# dev_efm32_tg.net
KiCad netlist of a schematic drawn in EAGLE
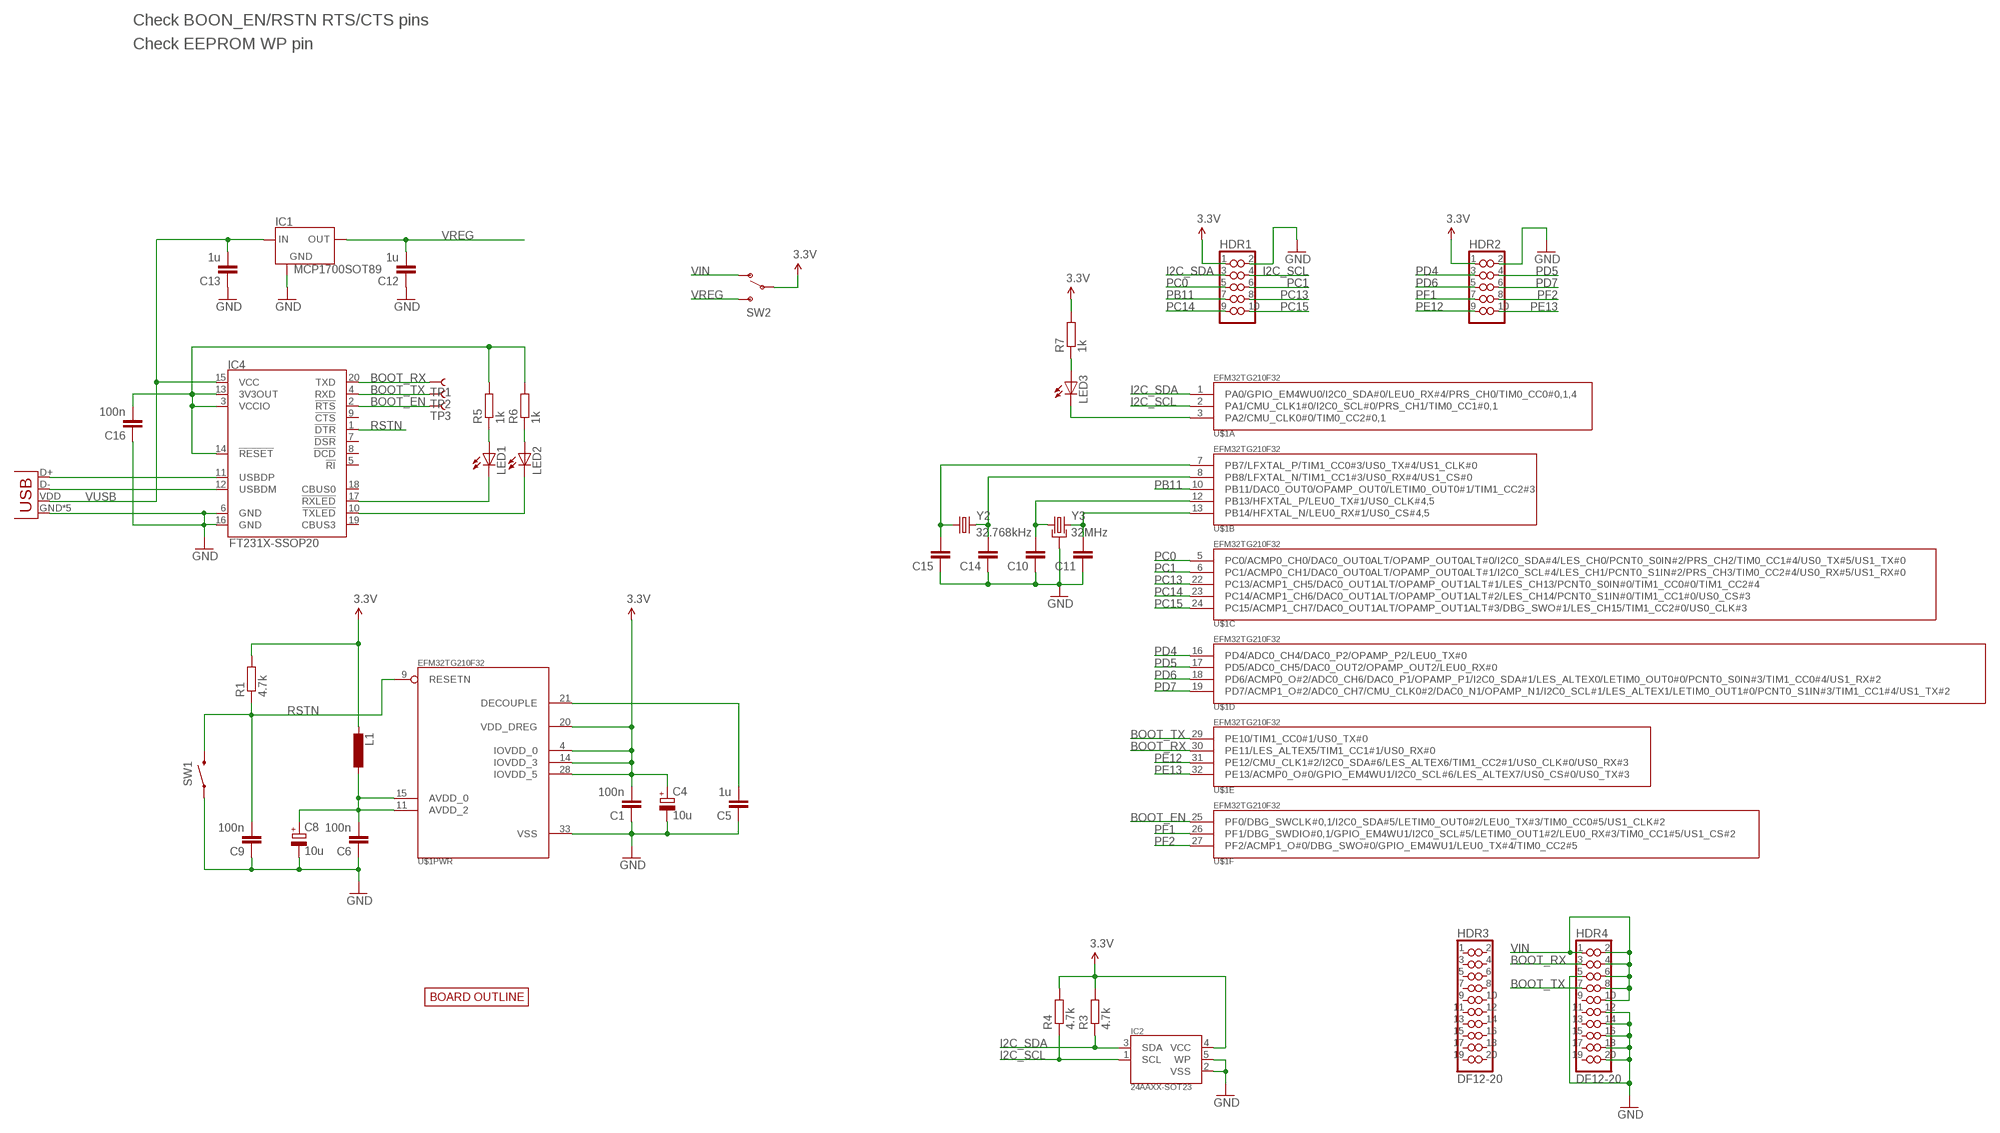
[diagram p0: schematic, sheet 1]

(export (version "E")
  (design (tool "Eeschema 10.0.6"))
  (components
    (comp (ref "C1")
      (value "100n")
      (footprint "eagle-import:0402")
      (libsource (lib "eagle-import") (part "C-0402"))
    )
    (comp (ref "C4")
      (value "10u")
      (footprint "eagle-import:CAP_CASE_A")
      (libsource (lib "eagle-import") (part "CPOL-A"))
    )
    (comp (ref "C5")
      (value "1u")
      (footprint "eagle-import:0402")
      (libsource (lib "eagle-import") (part "C-0402"))
    )
    (comp (ref "C6")
      (value "100n")
      (footprint "eagle-import:0402")
      (libsource (lib "eagle-import") (part "C-0402"))
    )
    (comp (ref "C8")
      (value "10u")
      (footprint "eagle-import:CAP_CASE_A")
      (libsource (lib "eagle-import") (part "CPOL-A"))
    )
    (comp (ref "C9")
      (value "100n")
      (footprint "eagle-import:0402")
      (libsource (lib "eagle-import") (part "C-0402"))
    )
    (comp (ref "C10")
      (value "C-0402")
      (footprint "eagle-import:0402")
      (libsource (lib "eagle-import") (part "C-0402"))
    )
    (comp (ref "C11")
      (value "C-0402")
      (footprint "eagle-import:0402")
      (libsource (lib "eagle-import") (part "C-0402"))
    )
    (comp (ref "C12")
      (value "1u")
      (footprint "eagle-import:0402")
      (libsource (lib "eagle-import") (part "C-0402"))
    )
    (comp (ref "C13")
      (value "1u")
      (footprint "eagle-import:0402")
      (libsource (lib "eagle-import") (part "C-0402"))
    )
    (comp (ref "C14")
      (value "C-0402")
      (footprint "eagle-import:0402")
      (libsource (lib "eagle-import") (part "C-0402"))
    )
    (comp (ref "C15")
      (value "C-0402")
      (footprint "eagle-import:0402")
      (libsource (lib "eagle-import") (part "C-0402"))
    )
    (comp (ref "C16")
      (value "100n")
      (footprint "eagle-import:0402")
      (libsource (lib "eagle-import") (part "C-0402"))
    )
    (comp (ref "HDR1")
      (value "HDR2X05-ROUND")
      (footprint "eagle-import:2X05ROUND")
      (libsource (lib "eagle-import") (part "HDR2X05-ROUND"))
    )
    (comp (ref "HDR2")
      (value "HDR2X05-ROUND")
      (footprint "eagle-import:2X05ROUND")
      (libsource (lib "eagle-import") (part "HDR2X05-ROUND"))
    )
    (comp (ref "HDR3")
      (value "DF12-20")
      (footprint "eagle-import:DF12_20_MF")
      (libsource (lib "eagle-import") (part "DF12-20"))
    )
    (comp (ref "HDR4")
      (value "DF12-20")
      (footprint "eagle-import:DF12_20_MF")
      (libsource (lib "eagle-import") (part "DF12-20"))
    )
    (comp (ref "IC1")
      (value "MCP1700SOT89")
      (footprint "eagle-import:SOT89")
      (libsource (lib "eagle-import") (part "MCP1700SOT89"))
    )
    (comp (ref "IC2")
      (value "24AAXX-SOT23")
      (footprint "eagle-import:SOT23-5")
      (libsource (lib "eagle-import") (part "24AAXX-SOT23"))
    )
    (comp (ref "IC4")
      (value "FT231X-SSOP20")
      (footprint "eagle-import:SSOP20")
      (libsource (lib "eagle-import") (part "FT231X-SSOP20"))
    )
    (comp (ref "L1")
      (value "L-0402")
      (footprint "eagle-import:0402")
      (libsource (lib "eagle-import") (part "L-0402"))
    )
    (comp (ref "LED1")
      (value "LED0603")
      (footprint "eagle-import:LED-0603")
      (libsource (lib "eagle-import") (part "LED0603"))
    )
    (comp (ref "LED2")
      (value "LED0603")
      (footprint "eagle-import:LED-0603")
      (libsource (lib "eagle-import") (part "LED0603"))
    )
    (comp (ref "LED3")
      (value "LED0603")
      (footprint "eagle-import:LED-0603")
      (libsource (lib "eagle-import") (part "LED0603"))
    )
    (comp (ref "R1")
      (value "4.7k")
      (footprint "eagle-import:0402")
      (libsource (lib "eagle-import") (part "R-0402"))
    )
    (comp (ref "R3")
      (value "4.7k")
      (footprint "eagle-import:0402")
      (libsource (lib "eagle-import") (part "R-0402"))
    )
    (comp (ref "R4")
      (value "4.7k")
      (footprint "eagle-import:0402")
      (libsource (lib "eagle-import") (part "R-0402"))
    )
    (comp (ref "R5")
      (value "1k")
      (footprint "eagle-import:0402")
      (libsource (lib "eagle-import") (part "R-0402"))
    )
    (comp (ref "R6")
      (value "1k")
      (footprint "eagle-import:0402")
      (libsource (lib "eagle-import") (part "R-0402"))
    )
    (comp (ref "R7")
      (value "1k")
      (footprint "eagle-import:0402")
      (libsource (lib "eagle-import") (part "R-0402"))
    )
    (comp (ref "SW1")
      (value "SWITCH_TACTILE-B3U-1000P")
      (footprint "eagle-import:B3U-1000P")
      (libsource (lib "eagle-import") (part "SWITCH_TACTILE-B3U-1000P"))
    )
    (comp (ref "SW2")
      (value "SWITCH_SPDT-PCM")
      (footprint "eagle-import:PCM12SMTR")
      (libsource (lib "eagle-import") (part "SWITCH_SPDT-PCM"))
    )
    (comp (ref "TP1")
      (value "TP_1X1-1")
      (footprint "eagle-import:TP_1X1_1")
      (libsource (lib "eagle-import") (part "TP_1X1-1"))
    )
    (comp (ref "TP2")
      (value "TP_1X1-1")
      (footprint "eagle-import:TP_1X1_1")
      (libsource (lib "eagle-import") (part "TP_1X1-1"))
    )
    (comp (ref "TP3")
      (value "TP_1X1-1")
      (footprint "eagle-import:TP_1X1_1")
      (libsource (lib "eagle-import") (part "TP_1X1-1"))
    )
    (comp (ref "U$1")
      (value "EFM32TG210F32")
      (footprint "eagle-import:QFN32")
      (libsource (lib "eagle-import") (part "EFM32TG210F32"))
    )
    (comp (ref "U$2")
      (value "USB-MICRO")
      (footprint "eagle-import:10118194_0001LF")
      (libsource (lib "eagle-import") (part "USB-MICRO"))
    )
    (comp (ref "U$3")
      (value "QK-OUTLINE")
      (footprint "eagle-import:QK-OUTLINE")
      (libsource (lib "eagle-import") (part "QK-OUTLINE"))
    )
    (comp (ref "Y2")
      (value "32.768kHz")
      (footprint "eagle-import:ABS07")
      (libsource (lib "eagle-import") (part "CRYSTAL-2-ABS07"))
    )
    (comp (ref "Y3")
      (value "32MHz")
      (footprint "eagle-import:ABM8G")
      (libsource (lib "eagle-import") (part "CRYSTAL-4-ABM8G"))
    )
  )
  (nets
    (net (code "1") (name "/BOOT_EN") (class "Default")
      (node (ref "IC4") (pin "2") (pinfunction "~{RTS}_2") (pintype "bidirectional"))
      (node (ref "TP3") (pin "P$1") (pinfunction "1_P$1") (pintype "bidirectional"))
      (node (ref "U$1") (pin "25") (pinfunction "PF0/DBG_SWCLK#0,1/I2C0_SDA#5/LETIM0_OUT0#2/LEU0_TX#3/TIM0_CC0#5/US1_CLK#2_25") (pintype "bidirectional"))
    )
    (net (code "2") (name "/BOOT_RX") (class "Default")
      (node (ref "HDR4") (pin "3") (pinfunction "3_3") (pintype "passive"))
      (node (ref "IC4") (pin "20") (pinfunction "TXD_20") (pintype "bidirectional"))
      (node (ref "TP1") (pin "P$1") (pinfunction "1_P$1") (pintype "bidirectional"))
      (node (ref "U$1") (pin "30") (pinfunction "PE11/LES_ALTEX5/TIM1_CC1#1/US0_RX#0_30") (pintype "bidirectional"))
    )
    (net (code "3") (name "/BOOT_TX") (class "Default")
      (node (ref "HDR4") (pin "7") (pinfunction "7_7") (pintype "passive"))
      (node (ref "IC4") (pin "4") (pinfunction "RXD_4") (pintype "bidirectional"))
      (node (ref "TP2") (pin "P$1") (pinfunction "1_P$1") (pintype "bidirectional"))
      (node (ref "U$1") (pin "29") (pinfunction "PE10/TIM1_CC0#1/US0_TX#0_29") (pintype "bidirectional"))
    )
    (net (code "4") (name "/I2C_SCL") (class "Default")
      (node (ref "HDR1") (pin "4") (pinfunction "4_4") (pintype "passive"))
      (node (ref "IC2") (pin "1") (pinfunction "SCL_1") (pintype "bidirectional"))
      (node (ref "R4") (pin "1") (pinfunction "1_1") (pintype "passive"))
      (node (ref "U$1") (pin "2") (pinfunction "PA1/CMU_CLK1#0/I2C0_SCL#0/PRS_CH1/TIM0_CC1#0,1_2") (pintype "bidirectional"))
    )
    (net (code "5") (name "/I2C_SDA") (class "Default")
      (node (ref "HDR1") (pin "3") (pinfunction "3_3") (pintype "passive"))
      (node (ref "IC2") (pin "3") (pinfunction "SDA_3") (pintype "bidirectional"))
      (node (ref "R3") (pin "1") (pinfunction "1_1") (pintype "passive"))
      (node (ref "U$1") (pin "1") (pinfunction "PA0/GPIO_EM4WU0/I2C0_SDA#0/LEU0_RX#4/PRS_CH0/TIM0_CC0#0,1,4_1") (pintype "bidirectional"))
    )
    (net (code "6") (name "/PB11") (class "Default")
      (node (ref "HDR1") (pin "7") (pinfunction "7_7") (pintype "passive"))
      (node (ref "U$1") (pin "10") (pinfunction "PB11/DAC0_OUT0/OPAMP_OUT0/LETIM0_OUT0#1/TIM1_CC2#3_10") (pintype "bidirectional"))
    )
    (net (code "7") (name "/PC0") (class "Default")
      (node (ref "HDR1") (pin "5") (pinfunction "5_5") (pintype "passive"))
      (node (ref "U$1") (pin "5") (pinfunction "PC0/ACMP0_CH0/DAC0_OUT0ALT/OPAMP_OUT0ALT#0/I2C0_SDA#4/LES_CH0/PCNT0_S0IN#2/PRS_CH2/TIM0_CC1#4/US0_TX#5/US1_TX#0_5") (pintype "bidirectional"))
    )
    (net (code "8") (name "/PC1") (class "Default")
      (node (ref "HDR1") (pin "6") (pinfunction "6_6") (pintype "passive"))
      (node (ref "U$1") (pin "6") (pinfunction "PC1/ACMP0_CH1/DAC0_OUT0ALT/OPAMP_OUT0ALT#1/I2C0_SCL#4/LES_CH1/PCNT0_S1IN#2/PRS_CH3/TIM0_CC2#4/US0_RX#5/US1_RX#0_6") (pintype "bidirectional"))
    )
    (net (code "9") (name "/PC13") (class "Default")
      (node (ref "HDR1") (pin "8") (pinfunction "8_8") (pintype "passive"))
      (node (ref "U$1") (pin "22") (pinfunction "PC13/ACMP1_CH5/DAC0_OUT1ALT/OPAMP_OUT1ALT#1/LES_CH13/PCNT0_S0IN#0/TIM1_CC0#0/TIM1_CC2#4_22") (pintype "bidirectional"))
    )
    (net (code "10") (name "/PC14") (class "Default")
      (node (ref "HDR1") (pin "9") (pinfunction "9_9") (pintype "passive"))
      (node (ref "U$1") (pin "23") (pinfunction "PC14/ACMP1_CH6/DAC0_OUT1ALT/OPAMP_OUT1ALT#2/LES_CH14/PCNT0_S1IN#0/TIM1_CC1#0/US0_CS#3_23") (pintype "bidirectional"))
    )
    (net (code "11") (name "/PC15") (class "Default")
      (node (ref "HDR1") (pin "10") (pinfunction "10_10") (pintype "passive"))
      (node (ref "U$1") (pin "24") (pinfunction "PC15/ACMP1_CH7/DAC0_OUT1ALT/OPAMP_OUT1ALT#3/DBG_SWO#1/LES_CH15/TIM1_CC2#0/US0_CLK#3_24") (pintype "bidirectional"))
    )
    (net (code "12") (name "/PD4") (class "Default")
      (node (ref "HDR2") (pin "3") (pinfunction "3_3") (pintype "passive"))
      (node (ref "U$1") (pin "16") (pinfunction "PD4/ADC0_CH4/DAC0_P2/OPAMP_P2/LEU0_TX#0_16") (pintype "bidirectional"))
    )
    (net (code "13") (name "/PD5") (class "Default")
      (node (ref "HDR2") (pin "4") (pinfunction "4_4") (pintype "passive"))
      (node (ref "U$1") (pin "17") (pinfunction "PD5/ADC0_CH5/DAC0_OUT2/OPAMP_OUT2/LEU0_RX#0_17") (pintype "bidirectional"))
    )
    (net (code "14") (name "/PD6") (class "Default")
      (node (ref "HDR2") (pin "5") (pinfunction "5_5") (pintype "passive"))
      (node (ref "U$1") (pin "18") (pinfunction "PD6/ACMP0_O#2/ADC0_CH6/DAC0_P1/OPAMP_P1/I2C0_SDA#1/LES_ALTEX0/LETIM0_OUT0#0/PCNT0_S0IN#3/TIM1_CC0#4/US1_RX#2_18") (pintype "bidirectional"))
    )
    (net (code "15") (name "/PD7") (class "Default")
      (node (ref "HDR2") (pin "6") (pinfunction "6_6") (pintype "passive"))
      (node (ref "U$1") (pin "19") (pinfunction "PD7/ACMP1_O#2/ADC0_CH7/CMU_CLK0#2/DAC0_N1/OPAMP_N1/I2C0_SCL#1/LES_ALTEX1/LETIM0_OUT1#0/PCNT0_S1IN#3/TIM1_CC1#4/US1_TX#2_19") (pintype "bidirectional"))
    )
    (net (code "16") (name "/PE12") (class "Default")
      (node (ref "HDR2") (pin "9") (pinfunction "9_9") (pintype "passive"))
      (node (ref "U$1") (pin "31") (pinfunction "PE12/CMU_CLK1#2/I2C0_SDA#6/LES_ALTEX6/TIM1_CC2#1/US0_CLK#0/US0_RX#3_31") (pintype "bidirectional"))
    )
    (net (code "17") (name "/PE13") (class "Default")
      (node (ref "HDR2") (pin "10") (pinfunction "10_10") (pintype "passive"))
      (node (ref "U$1") (pin "32") (pinfunction "PE13/ACMP0_O#0/GPIO_EM4WU1/I2C0_SCL#6/LES_ALTEX7/US0_CS#0/US0_TX#3_32") (pintype "bidirectional"))
    )
    (net (code "18") (name "/PF1") (class "Default")
      (node (ref "HDR2") (pin "7") (pinfunction "7_7") (pintype "passive"))
      (node (ref "U$1") (pin "26") (pinfunction "PF1/DBG_SWDIO#0,1/GPIO_EM4WU1/I2C0_SCL#5/LETIM0_OUT1#2/LEU0_RX#3/TIM0_CC1#5/US1_CS#2_26") (pintype "bidirectional"))
    )
    (net (code "19") (name "/PF2") (class "Default")
      (node (ref "HDR2") (pin "8") (pinfunction "8_8") (pintype "passive"))
      (node (ref "U$1") (pin "27") (pinfunction "PF2/ACMP1_O#0/DBG_SWO#0/GPIO_EM4WU1/LEU0_TX#4/TIM0_CC2#5_27") (pintype "bidirectional"))
    )
    (net (code "20") (name "/RSTN") (class "Default")
      (node (ref "C9") (pin "2") (pinfunction "2_2") (pintype "passive"))
      (node (ref "IC4") (pin "1") (pinfunction "~{DTR}_1") (pintype "bidirectional"))
      (node (ref "R1") (pin "1") (pinfunction "1_1") (pintype "passive"))
      (node (ref "SW1") (pin "P$2") (pinfunction "2_P$2") (pintype "passive"))
      (node (ref "U$1") (pin "9") (pinfunction "RESETN_9") (pintype "passive"))
    )
    (net (code "21") (name "/VIN") (class "Default")
      (node (ref "HDR4") (pin "1") (pinfunction "1_1") (pintype "passive"))
      (node (ref "HDR4") (pin "10") (pinfunction "10_10") (pintype "passive"))
      (node (ref "HDR4") (pin "2") (pinfunction "2_2") (pintype "passive"))
      (node (ref "HDR4") (pin "4") (pinfunction "4_4") (pintype "passive"))
      (node (ref "HDR4") (pin "6") (pinfunction "6_6") (pintype "passive"))
      (node (ref "HDR4") (pin "8") (pinfunction "8_8") (pintype "passive"))
      (node (ref "SW2") (pin "1") (pinfunction "1_1") (pintype "passive"))
    )
    (net (code "22") (name "/VREG") (class "Default")
      (node (ref "C12") (pin "2") (pinfunction "2_2") (pintype "passive"))
      (node (ref "IC1") (pin "3") (pinfunction "OUT_3") (pintype "output"))
      (node (ref "SW2") (pin "3") (pinfunction "2_3") (pintype "passive"))
    )
    (net (code "23") (name "/VUSB") (class "Default")
      (node (ref "C13") (pin "2") (pinfunction "2_2") (pintype "passive"))
      (node (ref "IC1") (pin "2") (pinfunction "IN_2") (pintype "input"))
      (node (ref "IC1") (pin "4") (pinfunction "IN_4") (pintype "input"))
      (node (ref "IC4") (pin "15") (pinfunction "VCC_15") (pintype "bidirectional"))
      (node (ref "U$2") (pin "VDD") (pinfunction "VBUS_VDD") (pintype "bidirectional"))
    )
    (net (code "24") (name "3.3V") (class "Default")
      (node (ref "C1") (pin "2") (pinfunction "2_2") (pintype "passive"))
      (node (ref "C4") (pin "1") (pinfunction "+_1") (pintype "passive"))
      (node (ref "HDR1") (pin "1") (pinfunction "1_1") (pintype "passive"))
      (node (ref "HDR2") (pin "1") (pinfunction "1_1") (pintype "passive"))
      (node (ref "IC2") (pin "4") (pinfunction "VCC_4") (pintype "power_in"))
      (node (ref "L1") (pin "2") (pinfunction "2_2") (pintype "passive"))
      (node (ref "R1") (pin "2") (pinfunction "2_2") (pintype "passive"))
      (node (ref "R3") (pin "2") (pinfunction "2_2") (pintype "passive"))
      (node (ref "R4") (pin "2") (pinfunction "2_2") (pintype "passive"))
      (node (ref "R7") (pin "2") (pinfunction "2_2") (pintype "passive"))
      (node (ref "SW2") (pin "2") (pinfunction "COM_2") (pintype "passive"))
      (node (ref "U$1") (pin "14") (pinfunction "IOVDD_3_14") (pintype "power_in"))
      (node (ref "U$1") (pin "20") (pinfunction "VDD_DREG_20") (pintype "power_in"))
      (node (ref "U$1") (pin "28") (pinfunction "IOVDD_5_28") (pintype "power_in"))
      (node (ref "U$1") (pin "4") (pinfunction "IOVDD_0_4") (pintype "power_in"))
    )
    (net (code "25") (name "GND") (class "Default")
      (node (ref "C1") (pin "1") (pinfunction "1_1") (pintype "passive"))
      (node (ref "C10") (pin "1") (pinfunction "1_1") (pintype "passive"))
      (node (ref "C11") (pin "1") (pinfunction "1_1") (pintype "passive"))
      (node (ref "C12") (pin "1") (pinfunction "1_1") (pintype "passive"))
      (node (ref "C13") (pin "1") (pinfunction "1_1") (pintype "passive"))
      (node (ref "C14") (pin "1") (pinfunction "1_1") (pintype "passive"))
      (node (ref "C15") (pin "1") (pinfunction "1_1") (pintype "passive"))
      (node (ref "C16") (pin "1") (pinfunction "1_1") (pintype "passive"))
      (node (ref "C4") (pin "2") (pinfunction "-_2") (pintype "passive"))
      (node (ref "C5") (pin "1") (pinfunction "1_1") (pintype "passive"))
      (node (ref "C6") (pin "1") (pinfunction "1_1") (pintype "passive"))
      (node (ref "C8") (pin "2") (pinfunction "-_2") (pintype "passive"))
      (node (ref "C9") (pin "1") (pinfunction "1_1") (pintype "passive"))
      (node (ref "HDR1") (pin "2") (pinfunction "2_2") (pintype "passive"))
      (node (ref "HDR2") (pin "2") (pinfunction "2_2") (pintype "passive"))
      (node (ref "HDR4") (pin "12") (pinfunction "12_12") (pintype "passive"))
      (node (ref "HDR4") (pin "14") (pinfunction "14_14") (pintype "passive"))
      (node (ref "HDR4") (pin "16") (pinfunction "16_16") (pintype "passive"))
      (node (ref "HDR4") (pin "18") (pinfunction "18_18") (pintype "passive"))
      (node (ref "HDR4") (pin "20") (pinfunction "20_20") (pintype "passive"))
      (node (ref "HDR4") (pin "5") (pinfunction "5_5") (pintype "passive"))
      (node (ref "IC1") (pin "1") (pinfunction "GND_1") (pintype "power_in"))
      (node (ref "IC2") (pin "2") (pinfunction "VSS_2") (pintype "power_in"))
      (node (ref "IC2") (pin "5") (pinfunction "WP_5") (pintype "bidirectional"))
      (node (ref "IC4") (pin "16") (pinfunction "GND_16") (pintype "bidirectional"))
      (node (ref "IC4") (pin "6") (pinfunction "GND_6") (pintype "bidirectional"))
      (node (ref "SW1") (pin "P$1") (pinfunction "1_P$1") (pintype "passive"))
      (node (ref "U$1") (pin "33") (pinfunction "VSS_33") (pintype "power_in"))
      (node (ref "U$2") (pin "GND") (pinfunction "GND_GND") (pintype "bidirectional"))
      (node (ref "U$2") (pin "PAD1") (pinfunction "GND_PAD1") (pintype "bidirectional"))
      (node (ref "U$2") (pin "PAD2") (pinfunction "GND_PAD2") (pintype "bidirectional"))
      (node (ref "U$2") (pin "SHIELD1") (pinfunction "GND_SHIELD1") (pintype "bidirectional"))
      (node (ref "U$2") (pin "SHIELD2") (pinfunction "GND_SHIELD2") (pintype "bidirectional"))
      (node (ref "Y3") (pin "2") (pinfunction "SHIELD_2") (pintype "power_in"))
      (node (ref "Y3") (pin "4") (pinfunction "SHIELD_4") (pintype "power_in"))
    )
    (net (code "26") (name "Net-(C8-+)") (class "Default")
      (node (ref "C6") (pin "2") (pinfunction "2_2") (pintype "passive"))
      (node (ref "C8") (pin "1") (pinfunction "+_1") (pintype "passive"))
      (node (ref "L1") (pin "1") (pinfunction "1_1") (pintype "passive"))
      (node (ref "U$1") (pin "11") (pinfunction "AVDD_2_11") (pintype "power_in"))
      (node (ref "U$1") (pin "15") (pinfunction "AVDD_0_15") (pintype "power_in"))
    )
    (net (code "27") (name "Net-(IC4-3V3OUT)") (class "Default")
      (node (ref "C16") (pin "2") (pinfunction "2_2") (pintype "passive"))
      (node (ref "IC4") (pin "13") (pinfunction "3V3OUT_13") (pintype "bidirectional"))
      (node (ref "IC4") (pin "14") (pinfunction "~{RESET}_14") (pintype "bidirectional"))
      (node (ref "IC4") (pin "3") (pinfunction "VCCIO_3") (pintype "bidirectional"))
      (node (ref "R5") (pin "2") (pinfunction "2_2") (pintype "passive"))
      (node (ref "R6") (pin "2") (pinfunction "2_2") (pintype "passive"))
    )
    (net (code "28") (name "Net-(IC4-USBDM)") (class "Default")
      (node (ref "IC4") (pin "12") (pinfunction "USBDM_12") (pintype "bidirectional"))
      (node (ref "U$2") (pin "D-") (pinfunction "D-_D-") (pintype "bidirectional"))
    )
    (net (code "29") (name "Net-(IC4-USBDP)") (class "Default")
      (node (ref "IC4") (pin "11") (pinfunction "USBDP_11") (pintype "bidirectional"))
      (node (ref "U$2") (pin "D+") (pinfunction "D+_D+") (pintype "bidirectional"))
    )
    (net (code "30") (name "Net-(IC4-~{RXLED})") (class "Default")
      (node (ref "IC4") (pin "17") (pinfunction "~{RXLED}_17") (pintype "bidirectional"))
      (node (ref "LED1") (pin "C") (pinfunction "C_C") (pintype "passive"))
    )
    (net (code "31") (name "Net-(IC4-~{TXLED})") (class "Default")
      (node (ref "IC4") (pin "10") (pinfunction "~{TXLED}_10") (pintype "bidirectional"))
      (node (ref "LED2") (pin "C") (pinfunction "C_C") (pintype "passive"))
    )
    (net (code "32") (name "Net-(LED1-PadA)") (class "Default")
      (node (ref "LED1") (pin "A") (pinfunction "A_A") (pintype "passive"))
      (node (ref "R5") (pin "1") (pinfunction "1_1") (pintype "passive"))
    )
    (net (code "33") (name "Net-(LED2-PadA)") (class "Default")
      (node (ref "LED2") (pin "A") (pinfunction "A_A") (pintype "passive"))
      (node (ref "R6") (pin "1") (pinfunction "1_1") (pintype "passive"))
    )
    (net (code "34") (name "Net-(LED3-PadA)") (class "Default")
      (node (ref "LED3") (pin "A") (pinfunction "A_A") (pintype "passive"))
      (node (ref "R7") (pin "1") (pinfunction "1_1") (pintype "passive"))
    )
    (net (code "35") (name "Net-(U$1A-PA2{slash}CMU_CLK0#0{slash}TIM0_CC2#0,1)") (class "Default")
      (node (ref "LED3") (pin "C") (pinfunction "C_C") (pintype "passive"))
      (node (ref "U$1") (pin "3") (pinfunction "PA2/CMU_CLK0#0/TIM0_CC2#0,1_3") (pintype "bidirectional"))
    )
    (net (code "36") (name "Net-(U$1B-PB7{slash}LFXTAL_P{slash}TIM1_CC0#3{slash}US0_TX#4{slash}US1_CLK#0)") (class "Default")
      (node (ref "C15") (pin "2") (pinfunction "2_2") (pintype "passive"))
      (node (ref "U$1") (pin "7") (pinfunction "PB7/LFXTAL_P/TIM1_CC0#3/US0_TX#4/US1_CLK#0_7") (pintype "bidirectional"))
      (node (ref "Y2") (pin "P$1") (pinfunction "1_P$1") (pintype "passive"))
    )
    (net (code "37") (name "Net-(U$1B-PB8{slash}LFXTAL_N{slash}TIM1_CC1#3{slash}US0_RX#4{slash}US1_CS#0)") (class "Default")
      (node (ref "C14") (pin "2") (pinfunction "2_2") (pintype "passive"))
      (node (ref "U$1") (pin "8") (pinfunction "PB8/LFXTAL_N/TIM1_CC1#3/US0_RX#4/US1_CS#0_8") (pintype "bidirectional"))
      (node (ref "Y2") (pin "P$2") (pinfunction "2_P$2") (pintype "passive"))
    )
    (net (code "38") (name "Net-(U$1B-PB13{slash}HFXTAL_P{slash}LEU0_TX#1{slash}US0_CLK#4,5)") (class "Default")
      (node (ref "C10") (pin "2") (pinfunction "2_2") (pintype "passive"))
      (node (ref "U$1") (pin "12") (pinfunction "PB13/HFXTAL_P/LEU0_TX#1/US0_CLK#4,5_12") (pintype "bidirectional"))
      (node (ref "Y3") (pin "1") (pinfunction "1_1") (pintype "passive"))
    )
    (net (code "39") (name "Net-(U$1B-PB14{slash}HFXTAL_N{slash}LEU0_RX#1{slash}US0_CS#4,5)") (class "Default")
      (node (ref "C11") (pin "2") (pinfunction "2_2") (pintype "passive"))
      (node (ref "U$1") (pin "13") (pinfunction "PB14/HFXTAL_N/LEU0_RX#1/US0_CS#4,5_13") (pintype "bidirectional"))
      (node (ref "Y3") (pin "3") (pinfunction "2_3") (pintype "passive"))
    )
    (net (code "40") (name "Net-(U$1G-DECOUPLE)") (class "Default")
      (node (ref "C5") (pin "2") (pinfunction "2_2") (pintype "passive"))
      (node (ref "U$1") (pin "21") (pinfunction "DECOUPLE_21") (pintype "power_in"))
    )
    (net (code "41") (name "unconnected-(HDR3-Pad1)") (class "Default")
      (node (ref "HDR3") (pin "1") (pinfunction "1_1") (pintype "passive"))
    )
    (net (code "42") (name "unconnected-(HDR3-Pad2)") (class "Default")
      (node (ref "HDR3") (pin "2") (pinfunction "2_2") (pintype "passive"))
    )
    (net (code "43") (name "unconnected-(HDR3-Pad3)") (class "Default")
      (node (ref "HDR3") (pin "3") (pinfunction "3_3") (pintype "passive"))
    )
    (net (code "44") (name "unconnected-(HDR3-Pad4)") (class "Default")
      (node (ref "HDR3") (pin "4") (pinfunction "4_4") (pintype "passive"))
    )
    (net (code "45") (name "unconnected-(HDR3-Pad5)") (class "Default")
      (node (ref "HDR3") (pin "5") (pinfunction "5_5") (pintype "passive"))
    )
    (net (code "46") (name "unconnected-(HDR3-Pad6)") (class "Default")
      (node (ref "HDR3") (pin "6") (pinfunction "6_6") (pintype "passive"))
    )
    (net (code "47") (name "unconnected-(HDR3-Pad7)") (class "Default")
      (node (ref "HDR3") (pin "7") (pinfunction "7_7") (pintype "passive"))
    )
    (net (code "48") (name "unconnected-(HDR3-Pad8)") (class "Default")
      (node (ref "HDR3") (pin "8") (pinfunction "8_8") (pintype "passive"))
    )
    (net (code "49") (name "unconnected-(HDR3-Pad9)") (class "Default")
      (node (ref "HDR3") (pin "9") (pinfunction "9_9") (pintype "passive"))
    )
    (net (code "50") (name "unconnected-(HDR3-Pad10)") (class "Default")
      (node (ref "HDR3") (pin "10") (pinfunction "10_10") (pintype "passive"))
    )
    (net (code "51") (name "unconnected-(HDR3-Pad11)") (class "Default")
      (node (ref "HDR3") (pin "11") (pinfunction "11_11") (pintype "passive"))
    )
    (net (code "52") (name "unconnected-(HDR3-Pad12)") (class "Default")
      (node (ref "HDR3") (pin "12") (pinfunction "12_12") (pintype "passive"))
    )
    (net (code "53") (name "unconnected-(HDR3-Pad13)") (class "Default")
      (node (ref "HDR3") (pin "13") (pinfunction "13_13") (pintype "passive"))
    )
    (net (code "54") (name "unconnected-(HDR3-Pad14)") (class "Default")
      (node (ref "HDR3") (pin "14") (pinfunction "14_14") (pintype "passive"))
    )
    (net (code "55") (name "unconnected-(HDR3-Pad15)") (class "Default")
      (node (ref "HDR3") (pin "15") (pinfunction "15_15") (pintype "passive"))
    )
    (net (code "56") (name "unconnected-(HDR3-Pad16)") (class "Default")
      (node (ref "HDR3") (pin "16") (pinfunction "16_16") (pintype "passive"))
    )
    (net (code "57") (name "unconnected-(HDR3-Pad17)") (class "Default")
      (node (ref "HDR3") (pin "17") (pinfunction "17_17") (pintype "passive"))
    )
    (net (code "58") (name "unconnected-(HDR3-Pad18)") (class "Default")
      (node (ref "HDR3") (pin "18") (pinfunction "18_18") (pintype "passive"))
    )
    (net (code "59") (name "unconnected-(HDR3-Pad19)") (class "Default")
      (node (ref "HDR3") (pin "19") (pinfunction "19_19") (pintype "passive"))
    )
    (net (code "60") (name "unconnected-(HDR3-Pad20)") (class "Default")
      (node (ref "HDR3") (pin "20") (pinfunction "20_20") (pintype "passive"))
    )
    (net (code "61") (name "unconnected-(HDR4-Pad9)") (class "Default")
      (node (ref "HDR4") (pin "9") (pinfunction "9_9") (pintype "passive"))
    )
    (net (code "62") (name "unconnected-(HDR4-Pad11)") (class "Default")
      (node (ref "HDR4") (pin "11") (pinfunction "11_11") (pintype "passive"))
    )
    (net (code "63") (name "unconnected-(HDR4-Pad13)") (class "Default")
      (node (ref "HDR4") (pin "13") (pinfunction "13_13") (pintype "passive"))
    )
    (net (code "64") (name "unconnected-(HDR4-Pad15)") (class "Default")
      (node (ref "HDR4") (pin "15") (pinfunction "15_15") (pintype "passive"))
    )
    (net (code "65") (name "unconnected-(HDR4-Pad17)") (class "Default")
      (node (ref "HDR4") (pin "17") (pinfunction "17_17") (pintype "passive"))
    )
    (net (code "66") (name "unconnected-(HDR4-Pad19)") (class "Default")
      (node (ref "HDR4") (pin "19") (pinfunction "19_19") (pintype "passive"))
    )
    (net (code "67") (name "unconnected-(IC4-CBUS0-Pad18)") (class "Default")
      (node (ref "IC4") (pin "18") (pinfunction "CBUS0_18") (pintype "bidirectional"))
    )
    (net (code "68") (name "unconnected-(IC4-CBUS3-Pad19)") (class "Default")
      (node (ref "IC4") (pin "19") (pinfunction "CBUS3_19") (pintype "bidirectional"))
    )
    (net (code "69") (name "unconnected-(IC4-~{CTS}-Pad9)") (class "Default")
      (node (ref "IC4") (pin "9") (pinfunction "~{CTS}_9") (pintype "bidirectional"))
    )
    (net (code "70") (name "unconnected-(IC4-~{DCD}-Pad8)") (class "Default")
      (node (ref "IC4") (pin "8") (pinfunction "~{DCD}_8") (pintype "bidirectional"))
    )
    (net (code "71") (name "unconnected-(IC4-~{DSR}-Pad7)") (class "Default")
      (node (ref "IC4") (pin "7") (pinfunction "~{DSR}_7") (pintype "bidirectional"))
    )
    (net (code "72") (name "unconnected-(IC4-~{RI}-Pad5)") (class "Default")
      (node (ref "IC4") (pin "5") (pinfunction "~{RI}_5") (pintype "bidirectional"))
    )
  )
)
